# LaserScanner.net
KiCad netlist of a schematic drawn in EAGLE
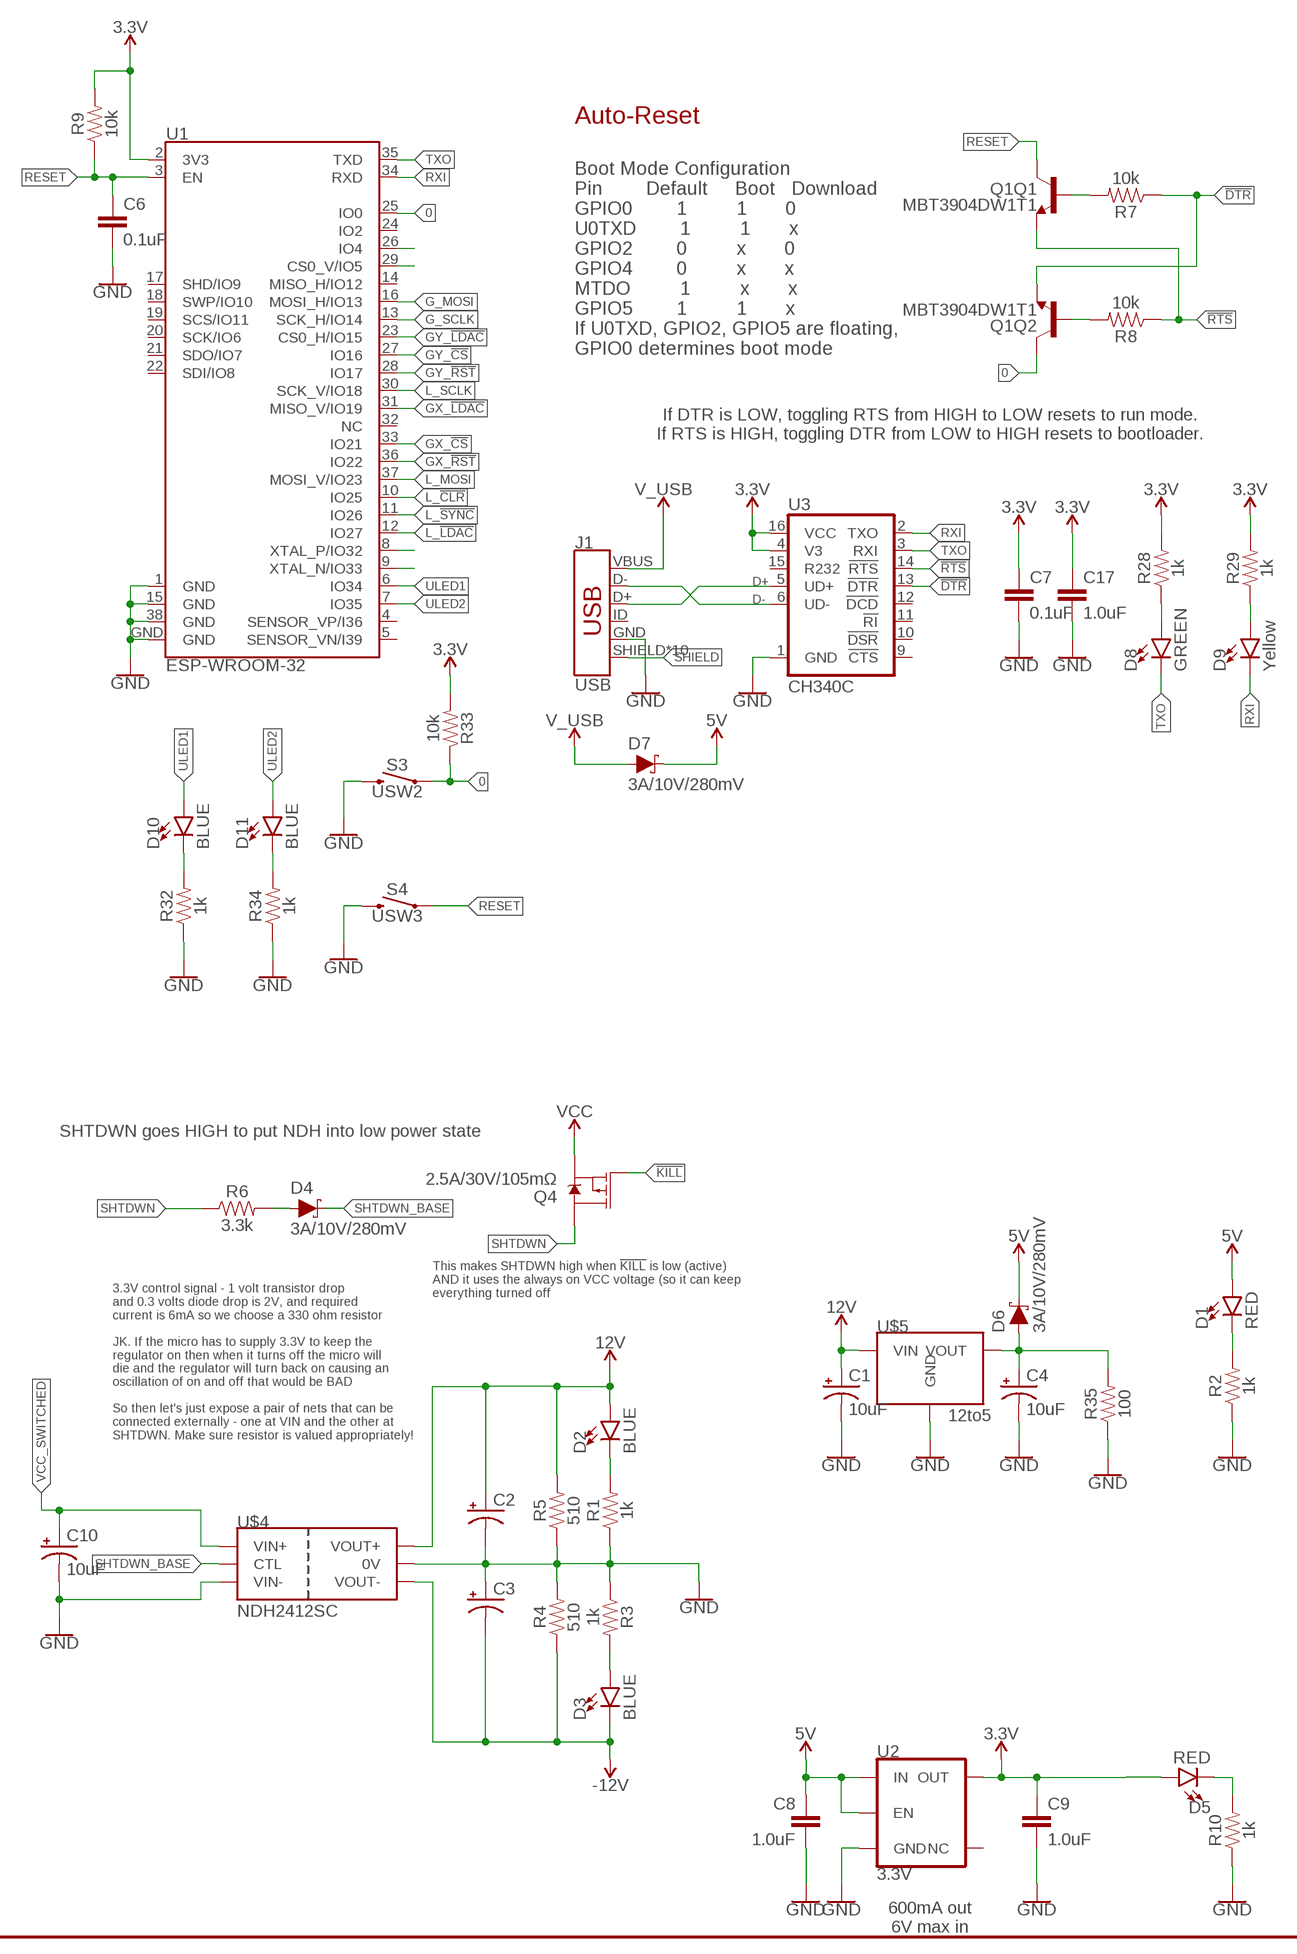
[diagram p0: schematic, sheet 1, part 1 of 2]
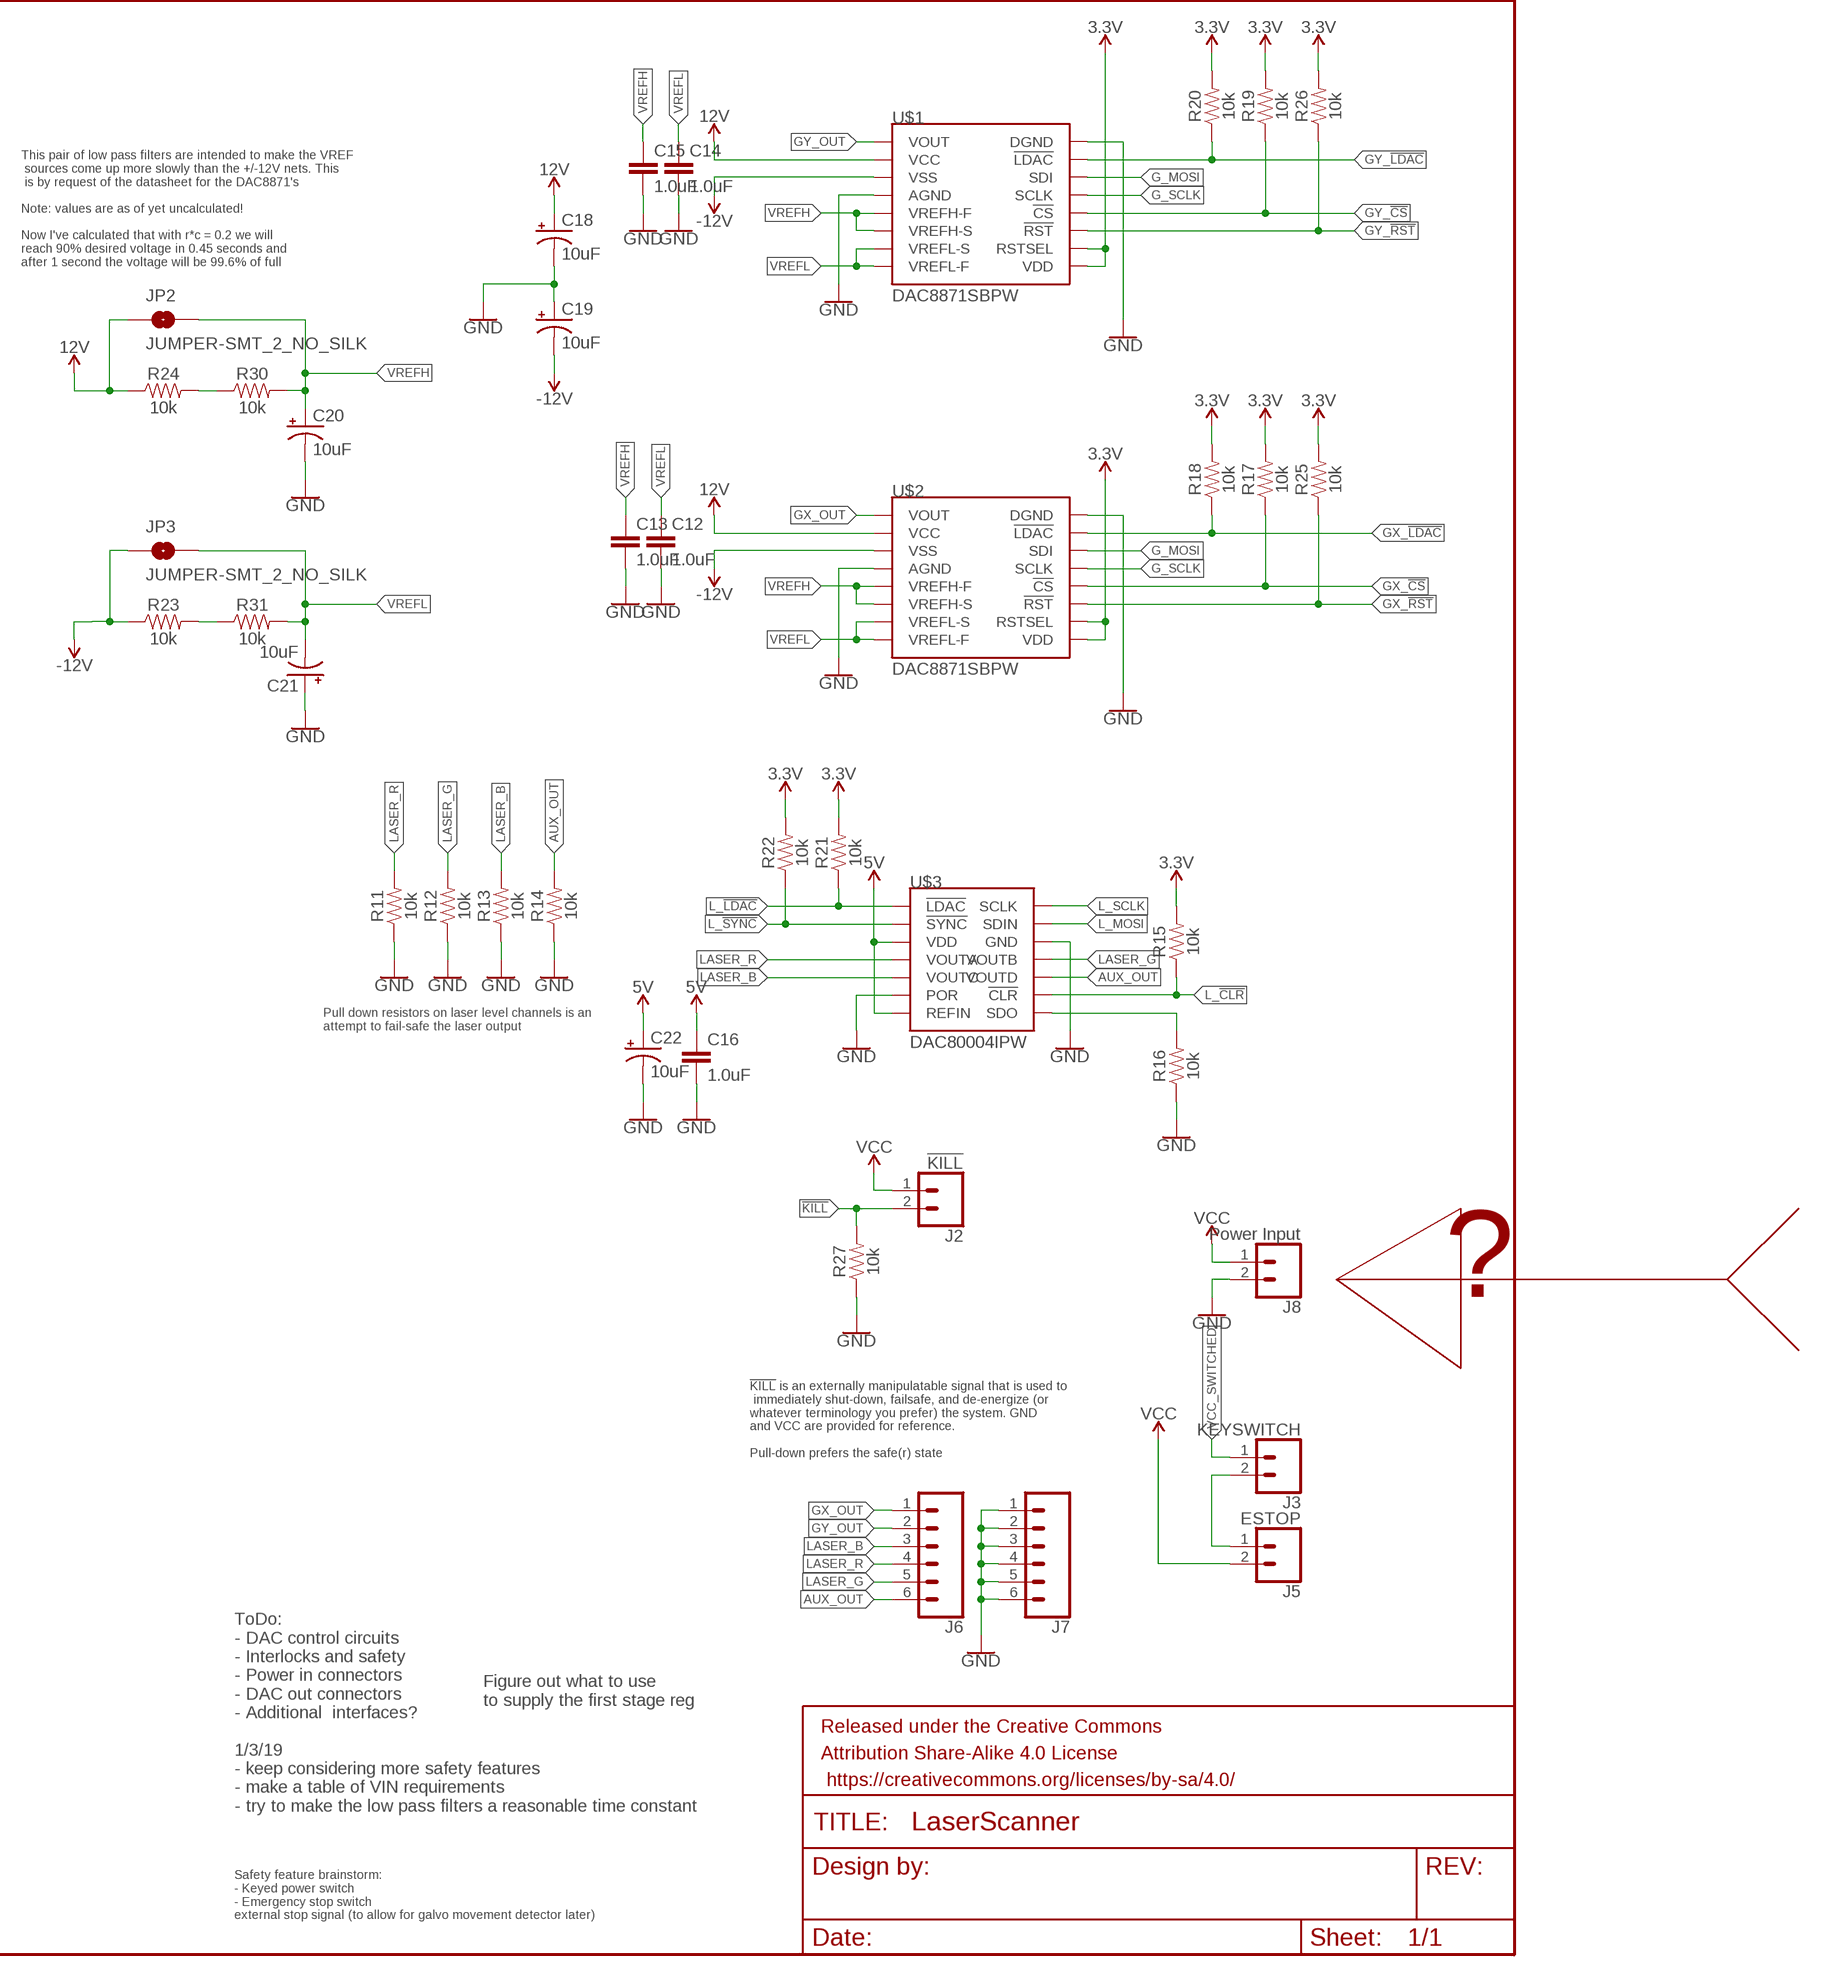
[diagram p1: schematic, sheet 1, part 2 of 2]

(export (version "E")
  (design (tool "Eeschema 10.0.6"))
  (components
    (comp (ref "C1")
      (value "10uF")
      (footprint "eagle-import:EIA3216")
      (libsource (lib "eagle-import") (part "10UF-POLAR-EIA3216-16V-10%(TANT)"))
    )
    (comp (ref "C2")
      (value "47UF-POLAR-PANASONIC_D-50V-20%")
      (footprint "eagle-import:PANASONIC_D")
      (libsource (lib "eagle-import") (part "47UF-POLAR-PANASONIC_D-50V-20%"))
    )
    (comp (ref "C3")
      (value "47UF-POLAR-PANASONIC_D-50V-20%")
      (footprint "eagle-import:PANASONIC_D")
      (libsource (lib "eagle-import") (part "47UF-POLAR-PANASONIC_D-50V-20%"))
    )
    (comp (ref "C4")
      (value "10uF")
      (footprint "eagle-import:EIA3216")
      (libsource (lib "eagle-import") (part "10UF-POLAR-EIA3216-16V-10%(TANT)"))
    )
    (comp (ref "C6")
      (value "0.1uF")
      (footprint "eagle-import:0603")
      (libsource (lib "eagle-import") (part "0.1UF-0603-25V-(+80/-20%)"))
    )
    (comp (ref "C7")
      (value "0.1uF")
      (footprint "eagle-import:0603")
      (libsource (lib "eagle-import") (part "0.1UF-0603-25V-5%"))
    )
    (comp (ref "C8")
      (value "1.0uF")
      (footprint "eagle-import:0603")
      (libsource (lib "eagle-import") (part "1.0UF-0603-16V-10%"))
    )
    (comp (ref "C9")
      (value "1.0uF")
      (footprint "eagle-import:0603")
      (libsource (lib "eagle-import") (part "1.0UF-0603-16V-10%"))
    )
    (comp (ref "C10")
      (value "10uF")
      (footprint "eagle-import:EIA3216")
      (libsource (lib "eagle-import") (part "10UF-POLAR-EIA3216-16V-10%(TANT)"))
    )
    (comp (ref "C12")
      (value "1.0uF")
      (footprint "eagle-import:0603")
      (libsource (lib "eagle-import") (part "1.0UF-0603-16V-10%-X7R"))
    )
    (comp (ref "C13")
      (value "1.0uF")
      (footprint "eagle-import:0603")
      (libsource (lib "eagle-import") (part "1.0UF-0603-16V-10%-X7R"))
    )
    (comp (ref "C14")
      (value "1.0uF")
      (footprint "eagle-import:0603")
      (libsource (lib "eagle-import") (part "1.0UF-0603-16V-10%-X7R"))
    )
    (comp (ref "C15")
      (value "1.0uF")
      (footprint "eagle-import:0603")
      (libsource (lib "eagle-import") (part "1.0UF-0603-16V-10%-X7R"))
    )
    (comp (ref "C16")
      (value "1.0uF")
      (footprint "eagle-import:0603")
      (libsource (lib "eagle-import") (part "1.0UF-0603-16V-10%-X7R"))
    )
    (comp (ref "C17")
      (value "1.0uF")
      (footprint "eagle-import:0603")
      (libsource (lib "eagle-import") (part "1.0UF-0603-16V-10%-X7R"))
    )
    (comp (ref "C18")
      (value "10uF")
      (footprint "eagle-import:EIA3216")
      (libsource (lib "eagle-import") (part "10UF-POLAR-EIA3216-16V-10%(TANT)"))
    )
    (comp (ref "C19")
      (value "10uF")
      (footprint "eagle-import:EIA3216")
      (libsource (lib "eagle-import") (part "10UF-POLAR-EIA3216-16V-10%(TANT)"))
    )
    (comp (ref "C20")
      (value "10uF")
      (footprint "eagle-import:EIA3216")
      (libsource (lib "eagle-import") (part "10UF-POLAR-EIA3216-16V-10%(TANT)"))
    )
    (comp (ref "C21")
      (value "10uF")
      (footprint "eagle-import:EIA3216")
      (libsource (lib "eagle-import") (part "10UF-POLAR-EIA3216-16V-10%(TANT)"))
    )
    (comp (ref "C22")
      (value "10uF")
      (footprint "eagle-import:EIA3216")
      (libsource (lib "eagle-import") (part "10UF-POLAR-EIA3216-16V-10%(TANT)"))
    )
    (comp (ref "D1")
      (value "RED")
      (footprint "eagle-import:LED-0603")
      (libsource (lib "eagle-import") (part "LED-RED0603"))
    )
    (comp (ref "D2")
      (value "BLUE")
      (footprint "eagle-import:LED-0603")
      (libsource (lib "eagle-import") (part "LED-BLUE0603"))
    )
    (comp (ref "D3")
      (value "BLUE")
      (footprint "eagle-import:LED-0603")
      (libsource (lib "eagle-import") (part "LED-BLUE0603"))
    )
    (comp (ref "D4")
      (value "3A/10V/280mV")
      (footprint "eagle-import:SOD-323")
      (libsource (lib "eagle-import") (part "DIODE-SCHOTTKY-BAT60A"))
    )
    (comp (ref "D5")
      (value "RED")
      (footprint "eagle-import:LED-0603")
      (libsource (lib "eagle-import") (part "LED-RED0603"))
    )
    (comp (ref "D6")
      (value "3A/10V/280mV")
      (footprint "eagle-import:SOD-323")
      (libsource (lib "eagle-import") (part "DIODE-SCHOTTKY-BAT60A"))
    )
    (comp (ref "D7")
      (value "3A/10V/280mV")
      (footprint "eagle-import:SOD-323")
      (libsource (lib "eagle-import") (part "DIODE-SCHOTTKY-BAT60A"))
    )
    (comp (ref "D8")
      (value "GREEN")
      (footprint "eagle-import:LED-0603")
      (libsource (lib "eagle-import") (part "LED-GREEN0603"))
    )
    (comp (ref "D9")
      (value "Yellow")
      (footprint "eagle-import:LED-0603")
      (libsource (lib "eagle-import") (part "LED-YELLOW0603"))
    )
    (comp (ref "D10")
      (value "BLUE")
      (footprint "eagle-import:LED-0603")
      (libsource (lib "eagle-import") (part "LED-BLUE0603"))
    )
    (comp (ref "D11")
      (value "BLUE")
      (footprint "eagle-import:LED-0603")
      (libsource (lib "eagle-import") (part "LED-BLUE0603"))
    )
    (comp (ref "FRAME1")
      (value "FRAME-LEDGER")
      (footprint "eagle-import:CREATIVE_COMMONS")
      (libsource (lib "eagle-import") (part "FRAME-LEDGER"))
    )
    (comp (ref "J1")
      (value "USB")
      (footprint "eagle-import:USB-MICROB-PTH-MILL")
      (libsource (lib "eagle-import") (part "USB_MICRO-B_HALF_PTH_MILL"))
    )
    (comp (ref "J2")
      (value "!KILL!")
      (footprint "eagle-import:1X02_NO_SILK")
      (libsource (lib "eagle-import") (part "CONN_021X02_NO_SILK"))
    )
    (comp (ref "J3")
      (value "KEYSWITCH")
      (footprint "eagle-import:1X02_NO_SILK")
      (libsource (lib "eagle-import") (part "CONN_021X02_NO_SILK"))
    )
    (comp (ref "J5")
      (value "ESTOP")
      (footprint "eagle-import:1X02_NO_SILK")
      (libsource (lib "eagle-import") (part "CONN_021X02_NO_SILK"))
    )
    (comp (ref "J6")
      (value "CONN_06NO_SILK_FEMALE_PTH")
      (footprint "eagle-import:1X06_NO_SILK")
      (libsource (lib "eagle-import") (part "CONN_06NO_SILK_FEMALE_PTH"))
    )
    (comp (ref "J7")
      (value "CONN_06NO_SILK_FEMALE_PTH")
      (footprint "eagle-import:1X06_NO_SILK")
      (libsource (lib "eagle-import") (part "CONN_06NO_SILK_FEMALE_PTH"))
    )
    (comp (ref "J8")
      (value "Power Input")
      (footprint "eagle-import:1X02_NO_SILK")
      (libsource (lib "eagle-import") (part "CONN_021X02_NO_SILK"))
    )
    (comp (ref "JP2")
      (value "JUMPER-SMT_2_NO_SILK")
      (footprint "eagle-import:SMT-JUMPER_2_NO_SILK")
      (libsource (lib "eagle-import") (part "JUMPER-SMT_2_NO_SILK"))
    )
    (comp (ref "JP3")
      (value "JUMPER-SMT_2_NO_SILK")
      (footprint "eagle-import:SMT-JUMPER_2_NO_SILK")
      (libsource (lib "eagle-import") (part "JUMPER-SMT_2_NO_SILK"))
    )
    (comp (ref "Q1")
      (value "MBT3904DW1T1")
      (footprint "eagle-import:SC70-6")
      (libsource (lib "eagle-import") (part "TRANS_NPN_DUAL-MBT3904DW1T1"))
    )
    (comp (ref "Q4")
      (value "2.5A/30V/105mΩ")
      (footprint "eagle-import:SOT23-3")
      (libsource (lib "eagle-import") (part "MOSFET_PCH-DMG2307L"))
    )
    (comp (ref "R1")
      (value "1k")
      (footprint "eagle-import:0603")
      (libsource (lib "eagle-import") (part "1KOHM-0603-1/10W-1%"))
    )
    (comp (ref "R2")
      (value "1k")
      (footprint "eagle-import:0603")
      (libsource (lib "eagle-import") (part "1KOHM-0603-1/10W-1%"))
    )
    (comp (ref "R3")
      (value "1k")
      (footprint "eagle-import:0603")
      (libsource (lib "eagle-import") (part "1KOHM-0603-1/10W-1%"))
    )
    (comp (ref "R4")
      (value "510")
      (footprint "eagle-import:2010")
      (libsource (lib "eagle-import") (part "510OHM-2010-1/2W-5%"))
    )
    (comp (ref "R5")
      (value "510")
      (footprint "eagle-import:2010")
      (libsource (lib "eagle-import") (part "510OHM-2010-1/2W-5%"))
    )
    (comp (ref "R6")
      (value "3.3k")
      (footprint "eagle-import:0603")
      (libsource (lib "eagle-import") (part "3.3KOHM-0603-1/10W-1%"))
    )
    (comp (ref "R7")
      (value "10k")
      (footprint "eagle-import:0603")
      (libsource (lib "eagle-import") (part "10KOHM-0603-1/10W-1%"))
    )
    (comp (ref "R8")
      (value "10k")
      (footprint "eagle-import:0603")
      (libsource (lib "eagle-import") (part "10KOHM-0603-1/10W-1%"))
    )
    (comp (ref "R9")
      (value "10k")
      (footprint "eagle-import:0603")
      (libsource (lib "eagle-import") (part "10KOHM-0603-1/10W-1%"))
    )
    (comp (ref "R10")
      (value "1k")
      (footprint "eagle-import:0603")
      (libsource (lib "eagle-import") (part "1KOHM-0603-1/10W-1%"))
    )
    (comp (ref "R11")
      (value "10k")
      (footprint "eagle-import:0603")
      (libsource (lib "eagle-import") (part "10KOHM-0603-1/10W-1%"))
    )
    (comp (ref "R12")
      (value "10k")
      (footprint "eagle-import:0603")
      (libsource (lib "eagle-import") (part "10KOHM-0603-1/10W-1%"))
    )
    (comp (ref "R13")
      (value "10k")
      (footprint "eagle-import:0603")
      (libsource (lib "eagle-import") (part "10KOHM-0603-1/10W-1%"))
    )
    (comp (ref "R14")
      (value "10k")
      (footprint "eagle-import:0603")
      (libsource (lib "eagle-import") (part "10KOHM-0603-1/10W-1%"))
    )
    (comp (ref "R15")
      (value "10k")
      (footprint "eagle-import:0603")
      (libsource (lib "eagle-import") (part "10KOHM-0603-1/10W-1%"))
    )
    (comp (ref "R16")
      (value "10k")
      (footprint "eagle-import:0603")
      (libsource (lib "eagle-import") (part "10KOHM-0603-1/10W-1%"))
    )
    (comp (ref "R17")
      (value "10k")
      (footprint "eagle-import:0603")
      (libsource (lib "eagle-import") (part "10KOHM-0603-1/10W-1%"))
    )
    (comp (ref "R18")
      (value "10k")
      (footprint "eagle-import:0603")
      (libsource (lib "eagle-import") (part "10KOHM-0603-1/10W-1%"))
    )
    (comp (ref "R19")
      (value "10k")
      (footprint "eagle-import:0603")
      (libsource (lib "eagle-import") (part "10KOHM-0603-1/10W-1%"))
    )
    (comp (ref "R20")
      (value "10k")
      (footprint "eagle-import:0603")
      (libsource (lib "eagle-import") (part "10KOHM-0603-1/10W-1%"))
    )
    (comp (ref "R21")
      (value "10k")
      (footprint "eagle-import:0603")
      (libsource (lib "eagle-import") (part "10KOHM-0603-1/10W-1%"))
    )
    (comp (ref "R22")
      (value "10k")
      (footprint "eagle-import:0603")
      (libsource (lib "eagle-import") (part "10KOHM-0603-1/10W-1%"))
    )
    (comp (ref "R23")
      (value "10k")
      (footprint "eagle-import:0603")
      (libsource (lib "eagle-import") (part "10KOHM-0603-1/10W-1%"))
    )
    (comp (ref "R24")
      (value "10k")
      (footprint "eagle-import:0603")
      (libsource (lib "eagle-import") (part "10KOHM-0603-1/10W-1%"))
    )
    (comp (ref "R25")
      (value "10k")
      (footprint "eagle-import:0603")
      (libsource (lib "eagle-import") (part "10KOHM-0603-1/10W-1%"))
    )
    (comp (ref "R26")
      (value "10k")
      (footprint "eagle-import:0603")
      (libsource (lib "eagle-import") (part "10KOHM-0603-1/10W-1%"))
    )
    (comp (ref "R27")
      (value "10k")
      (footprint "eagle-import:0603")
      (libsource (lib "eagle-import") (part "10KOHM-0603-1/10W-1%"))
    )
    (comp (ref "R28")
      (value "1k")
      (footprint "eagle-import:0603")
      (libsource (lib "eagle-import") (part "1KOHM-0603-1/10W-1%"))
    )
    (comp (ref "R29")
      (value "1k")
      (footprint "eagle-import:0603")
      (libsource (lib "eagle-import") (part "1KOHM-0603-1/10W-1%"))
    )
    (comp (ref "R30")
      (value "10k")
      (footprint "eagle-import:0603")
      (libsource (lib "eagle-import") (part "10KOHM-0603-1/10W-1%"))
    )
    (comp (ref "R31")
      (value "10k")
      (footprint "eagle-import:0603")
      (libsource (lib "eagle-import") (part "10KOHM-0603-1/10W-1%"))
    )
    (comp (ref "R32")
      (value "1k")
      (footprint "eagle-import:0603")
      (libsource (lib "eagle-import") (part "1KOHM-0603-1/10W-1%"))
    )
    (comp (ref "R33")
      (value "10k")
      (footprint "eagle-import:0603")
      (libsource (lib "eagle-import") (part "10KOHM-0603-1/10W-1%"))
    )
    (comp (ref "R34")
      (value "1k")
      (footprint "eagle-import:0603")
      (libsource (lib "eagle-import") (part "1KOHM-0603-1/10W-1%"))
    )
    (comp (ref "R35")
      (value "100")
      (footprint "eagle-import:0603")
      (libsource (lib "eagle-import") (part "100OHM-0603-1/4W-5%"))
    )
    (comp (ref "S3")
      (value "USW2")
      (footprint "eagle-import:TACTILE_SWITCH_SMD_5.2MM")
      (libsource (lib "eagle-import") (part "MOMENTARY-SWITCH-SPST-SMD-5.2-REDUNDANT"))
    )
    (comp (ref "S4")
      (value "USW3")
      (footprint "eagle-import:TACTILE_SWITCH_SMD_5.2MM")
      (libsource (lib "eagle-import") (part "MOMENTARY-SWITCH-SPST-SMD-5.2-REDUNDANT"))
    )
    (comp (ref "U$1")
      (value "DAC8871SBPW")
      (footprint "eagle-import:TSSOP16")
      (libsource (lib "eagle-import") (part "DAC8871SBPW"))
    )
    (comp (ref "U$2")
      (value "DAC8871SBPW")
      (footprint "eagle-import:TSSOP16")
      (libsource (lib "eagle-import") (part "DAC8871SBPW"))
    )
    (comp (ref "U$3")
      (value "DAC80004IPW")
      (footprint "eagle-import:TSSOP14")
      (libsource (lib "eagle-import") (part "DAC80004IPW"))
    )
    (comp (ref "U$4")
      (value "NDH2412SC")
      (footprint "eagle-import:NDH")
      (libsource (lib "eagle-import") (part "NDH2412SC"))
    )
    (comp (ref "U$5")
      (value "12to5")
      (footprint "eagle-import:RE-78E")
      (libsource (lib "eagle-import") (part "R-78E3.3-1.0"))
    )
    (comp (ref "U1")
      (value "ESP-WROOM-32")
      (footprint "eagle-import:ESP-WROOM-32")
      (libsource (lib "eagle-import") (part "ESP-WROOM-32"))
    )
    (comp (ref "U2")
      (value "3.3V")
      (footprint "eagle-import:SOT23-5")
      (libsource (lib "eagle-import") (part "V_REG_AP2112K-3.3V"))
    )
    (comp (ref "U3")
      (value "CH340C")
      (footprint "eagle-import:SO016")
      (libsource (lib "eagle-import") (part "CH340C"))
    )
  )
  (nets
    (net (code "1") (name "-12V") (class "Default")
      (node (ref "C19") (pin "-") (pinfunction "-_-") (pintype "passive"))
      (node (ref "C3") (pin "-") (pinfunction "-_-") (pintype "passive"))
      (node (ref "D3") (pin "C") (pinfunction "C_C") (pintype "passive"))
      (node (ref "JP3") (pin "1") (pinfunction "1_1") (pintype "passive"))
      (node (ref "R23") (pin "1") (pinfunction "1_1") (pintype "passive"))
      (node (ref "R4") (pin "1") (pinfunction "1_1") (pintype "passive"))
      (node (ref "U$1") (pin "3") (pinfunction "VSS_3") (pintype "bidirectional"))
      (node (ref "U$2") (pin "3") (pinfunction "VSS_3") (pintype "bidirectional"))
      (node (ref "U$4") (pin "9") (pinfunction "VOUT-_9") (pintype "bidirectional"))
    )
    (net (code "2") (name "/D+") (class "Default")
      (node (ref "J1") (pin "D+") (pinfunction "D+_D+") (pintype "bidirectional"))
      (node (ref "U3") (pin "5") (pinfunction "UD+_5") (pintype "bidirectional"))
    )
    (net (code "3") (name "/D-") (class "Default")
      (node (ref "J1") (pin "D-") (pinfunction "D-_D-") (pintype "bidirectional"))
      (node (ref "U3") (pin "6") (pinfunction "UD-_6") (pintype "bidirectional"))
    )
    (net (code "4") (name "/GX_~{CS}") (class "Default")
      (node (ref "R17") (pin "1") (pinfunction "1_1") (pintype "passive"))
      (node (ref "U$2") (pin "12") (pinfunction "~{CS}_12") (pintype "bidirectional"))
      (node (ref "U1") (pin "33") (pinfunction "IO21_33") (pintype "bidirectional"))
    )
    (net (code "5") (name "/GX_~{LDAC}") (class "Default")
      (node (ref "R18") (pin "1") (pinfunction "1_1") (pintype "passive"))
      (node (ref "U$2") (pin "15") (pinfunction "~{LDAC}_15") (pintype "bidirectional"))
      (node (ref "U1") (pin "31") (pinfunction "MISO_V/IO19_31") (pintype "bidirectional"))
    )
    (net (code "6") (name "/GX_~{RST}") (class "Default")
      (node (ref "R25") (pin "1") (pinfunction "1_1") (pintype "passive"))
      (node (ref "U$2") (pin "11") (pinfunction "~{RST}_11") (pintype "bidirectional"))
      (node (ref "U1") (pin "36") (pinfunction "IO22_36") (pintype "bidirectional"))
    )
    (net (code "7") (name "/GY_~{CS}") (class "Default")
      (node (ref "R19") (pin "1") (pinfunction "1_1") (pintype "passive"))
      (node (ref "U$1") (pin "12") (pinfunction "~{CS}_12") (pintype "bidirectional"))
      (node (ref "U1") (pin "27") (pinfunction "IO16_27") (pintype "bidirectional"))
    )
    (net (code "8") (name "/GY_~{LDAC}") (class "Default")
      (node (ref "R20") (pin "1") (pinfunction "1_1") (pintype "passive"))
      (node (ref "U$1") (pin "15") (pinfunction "~{LDAC}_15") (pintype "bidirectional"))
      (node (ref "U1") (pin "23") (pinfunction "CS0_H/IO15_23") (pintype "bidirectional"))
    )
    (net (code "9") (name "/GY_~{RST}") (class "Default")
      (node (ref "R26") (pin "1") (pinfunction "1_1") (pintype "passive"))
      (node (ref "U$1") (pin "11") (pinfunction "~{RST}_11") (pintype "bidirectional"))
      (node (ref "U1") (pin "28") (pinfunction "IO17_28") (pintype "bidirectional"))
    )
    (net (code "10") (name "/L_~{CLR}") (class "Default")
      (node (ref "R15") (pin "1") (pinfunction "1_1") (pintype "passive"))
      (node (ref "U$3") (pin "9") (pinfunction "~{CLR}_9") (pintype "bidirectional"))
      (node (ref "U1") (pin "10") (pinfunction "IO25_10") (pintype "bidirectional"))
    )
    (net (code "11") (name "/L_~{LDAC}") (class "Default")
      (node (ref "R21") (pin "1") (pinfunction "1_1") (pintype "passive"))
      (node (ref "U$3") (pin "1") (pinfunction "~{LDAC}_1") (pintype "bidirectional"))
      (node (ref "U1") (pin "12") (pinfunction "IO27_12") (pintype "bidirectional"))
    )
    (net (code "12") (name "/L_~{SYNC}") (class "Default")
      (node (ref "R22") (pin "1") (pinfunction "1_1") (pintype "passive"))
      (node (ref "U$3") (pin "2") (pinfunction "~{SYNC}_2") (pintype "bidirectional"))
      (node (ref "U1") (pin "11") (pinfunction "IO26_11") (pintype "bidirectional"))
    )
    (net (code "13") (name "/~{DTR}") (class "Default")
      (node (ref "Q1") (pin "1") (pinfunction "E_1") (pintype "passive"))
      (node (ref "R7") (pin "1") (pinfunction "1_1") (pintype "passive"))
      (node (ref "U3") (pin "13") (pinfunction "~{DTR}_13") (pintype "bidirectional"))
    )
    (net (code "14") (name "/~{KILL}") (class "Default")
      (node (ref "J2") (pin "2") (pinfunction "2_2") (pintype "passive"))
      (node (ref "Q4") (pin "1") (pinfunction "G_1") (pintype "bidirectional"))
      (node (ref "R27") (pin "2") (pinfunction "2_2") (pintype "passive"))
    )
    (net (code "15") (name "/~{RTS}") (class "Default")
      (node (ref "Q1") (pin "4") (pinfunction "E_4") (pintype "passive"))
      (node (ref "R8") (pin "1") (pinfunction "1_1") (pintype "passive"))
      (node (ref "U3") (pin "14") (pinfunction "~{RTS}_14") (pintype "bidirectional"))
    )
    (net (code "16") (name "0") (class "Default")
      (node (ref "Q1") (pin "6") (pinfunction "C_6") (pintype "passive"))
      (node (ref "R33") (pin "1") (pinfunction "1_1") (pintype "passive"))
      (node (ref "S3") (pin "1") (pinfunction "1_1") (pintype "passive"))
      (node (ref "S3") (pin "2") (pinfunction "1_2") (pintype "passive"))
      (node (ref "U1") (pin "25") (pinfunction "IO0_25") (pintype "bidirectional"))
    )
    (net (code "17") (name "3.3V") (class "Default")
      (node (ref "C17") (pin "1") (pinfunction "1_1") (pintype "passive"))
      (node (ref "C7") (pin "1") (pinfunction "1_1") (pintype "passive"))
      (node (ref "C9") (pin "1") (pinfunction "1_1") (pintype "passive"))
      (node (ref "D5") (pin "A") (pinfunction "A_A") (pintype "passive"))
      (node (ref "R15") (pin "2") (pinfunction "2_2") (pintype "passive"))
      (node (ref "R17") (pin "2") (pinfunction "2_2") (pintype "passive"))
      (node (ref "R18") (pin "2") (pinfunction "2_2") (pintype "passive"))
      (node (ref "R19") (pin "2") (pinfunction "2_2") (pintype "passive"))
      (node (ref "R20") (pin "2") (pinfunction "2_2") (pintype "passive"))
      (node (ref "R21") (pin "2") (pinfunction "2_2") (pintype "passive"))
      (node (ref "R22") (pin "2") (pinfunction "2_2") (pintype "passive"))
      (node (ref "R25") (pin "2") (pinfunction "2_2") (pintype "passive"))
      (node (ref "R26") (pin "2") (pinfunction "2_2") (pintype "passive"))
      (node (ref "R28") (pin "2") (pinfunction "2_2") (pintype "passive"))
      (node (ref "R29") (pin "2") (pinfunction "2_2") (pintype "passive"))
      (node (ref "R33") (pin "2") (pinfunction "2_2") (pintype "passive"))
      (node (ref "R9") (pin "2") (pinfunction "2_2") (pintype "passive"))
      (node (ref "U$1") (pin "10") (pinfunction "RSTSEL_10") (pintype "bidirectional"))
      (node (ref "U$1") (pin "9") (pinfunction "VDD_9") (pintype "bidirectional"))
      (node (ref "U$2") (pin "10") (pinfunction "RSTSEL_10") (pintype "bidirectional"))
      (node (ref "U$2") (pin "9") (pinfunction "VDD_9") (pintype "bidirectional"))
      (node (ref "U1") (pin "2") (pinfunction "3V3_2") (pintype "bidirectional"))
      (node (ref "U2") (pin "5") (pinfunction "OUT_5") (pintype "passive"))
      (node (ref "U3") (pin "16") (pinfunction "VCC_16") (pintype "bidirectional"))
      (node (ref "U3") (pin "4") (pinfunction "V3_4") (pintype "bidirectional"))
    )
    (net (code "18") (name "5V") (class "Default")
      (node (ref "C16") (pin "1") (pinfunction "1_1") (pintype "passive"))
      (node (ref "C22") (pin "+") (pinfunction "+_+") (pintype "passive"))
      (node (ref "C8") (pin "1") (pinfunction "1_1") (pintype "passive"))
      (node (ref "D1") (pin "A") (pinfunction "A_A") (pintype "passive"))
      (node (ref "D6") (pin "C") (pinfunction "C_C") (pintype "passive"))
      (node (ref "D7") (pin "C") (pinfunction "C_C") (pintype "passive"))
      (node (ref "U$3") (pin "3") (pinfunction "VDD_3") (pintype "bidirectional"))
      (node (ref "U$3") (pin "7") (pinfunction "REFIN_7") (pintype "bidirectional"))
      (node (ref "U2") (pin "1") (pinfunction "IN_1") (pintype "input"))
      (node (ref "U2") (pin "3") (pinfunction "EN_3") (pintype "input"))
    )
    (net (code "19") (name "12V") (class "Default")
      (node (ref "C1") (pin "+") (pinfunction "+_+") (pintype "passive"))
      (node (ref "C18") (pin "+") (pinfunction "+_+") (pintype "passive"))
      (node (ref "C2") (pin "+") (pinfunction "+_+") (pintype "passive"))
      (node (ref "D2") (pin "A") (pinfunction "A_A") (pintype "passive"))
      (node (ref "JP2") (pin "1") (pinfunction "1_1") (pintype "passive"))
      (node (ref "R24") (pin "1") (pinfunction "1_1") (pintype "passive"))
      (node (ref "R5") (pin "2") (pinfunction "2_2") (pintype "passive"))
      (node (ref "U$1") (pin "2") (pinfunction "VCC_2") (pintype "bidirectional"))
      (node (ref "U$2") (pin "2") (pinfunction "VCC_2") (pintype "bidirectional"))
      (node (ref "U$4") (pin "6") (pinfunction "VOUT+_6") (pintype "bidirectional"))
      (node (ref "U$5") (pin "1") (pinfunction "VIN_1") (pintype "bidirectional"))
    )
    (net (code "20") (name "AUX_OUT") (class "Default")
      (node (ref "J6") (pin "6") (pinfunction "6_6") (pintype "passive"))
      (node (ref "R14") (pin "2") (pinfunction "2_2") (pintype "passive"))
      (node (ref "U$3") (pin "10") (pinfunction "VOUTD_10") (pintype "bidirectional"))
    )
    (net (code "21") (name "GND") (class "Default")
      (node (ref "C1") (pin "-") (pinfunction "-_-") (pintype "passive"))
      (node (ref "C10") (pin "-") (pinfunction "-_-") (pintype "passive"))
      (node (ref "C12") (pin "2") (pinfunction "2_2") (pintype "passive"))
      (node (ref "C13") (pin "2") (pinfunction "2_2") (pintype "passive"))
      (node (ref "C14") (pin "2") (pinfunction "2_2") (pintype "passive"))
      (node (ref "C15") (pin "2") (pinfunction "2_2") (pintype "passive"))
      (node (ref "C16") (pin "2") (pinfunction "2_2") (pintype "passive"))
      (node (ref "C17") (pin "2") (pinfunction "2_2") (pintype "passive"))
      (node (ref "C18") (pin "-") (pinfunction "-_-") (pintype "passive"))
      (node (ref "C19") (pin "+") (pinfunction "+_+") (pintype "passive"))
      (node (ref "C2") (pin "-") (pinfunction "-_-") (pintype "passive"))
      (node (ref "C20") (pin "-") (pinfunction "-_-") (pintype "passive"))
      (node (ref "C21") (pin "+") (pinfunction "+_+") (pintype "passive"))
      (node (ref "C22") (pin "-") (pinfunction "-_-") (pintype "passive"))
      (node (ref "C3") (pin "+") (pinfunction "+_+") (pintype "passive"))
      (node (ref "C4") (pin "-") (pinfunction "-_-") (pintype "passive"))
      (node (ref "C6") (pin "2") (pinfunction "2_2") (pintype "passive"))
      (node (ref "C7") (pin "2") (pinfunction "2_2") (pintype "passive"))
      (node (ref "C8") (pin "2") (pinfunction "2_2") (pintype "passive"))
      (node (ref "C9") (pin "2") (pinfunction "2_2") (pintype "passive"))
      (node (ref "J1") (pin "GND") (pinfunction "GND_GND") (pintype "power_in"))
      (node (ref "J7") (pin "1") (pinfunction "1_1") (pintype "passive"))
      (node (ref "J7") (pin "2") (pinfunction "2_2") (pintype "passive"))
      (node (ref "J7") (pin "3") (pinfunction "3_3") (pintype "passive"))
      (node (ref "J7") (pin "4") (pinfunction "4_4") (pintype "passive"))
      (node (ref "J7") (pin "5") (pinfunction "5_5") (pintype "passive"))
      (node (ref "J7") (pin "6") (pinfunction "6_6") (pintype "passive"))
      (node (ref "J8") (pin "2") (pinfunction "2_2") (pintype "passive"))
      (node (ref "R1") (pin "1") (pinfunction "1_1") (pintype "passive"))
      (node (ref "R10") (pin "1") (pinfunction "1_1") (pintype "passive"))
      (node (ref "R11") (pin "1") (pinfunction "1_1") (pintype "passive"))
      (node (ref "R12") (pin "1") (pinfunction "1_1") (pintype "passive"))
      (node (ref "R13") (pin "1") (pinfunction "1_1") (pintype "passive"))
      (node (ref "R14") (pin "1") (pinfunction "1_1") (pintype "passive"))
      (node (ref "R16") (pin "1") (pinfunction "1_1") (pintype "passive"))
      (node (ref "R2") (pin "1") (pinfunction "1_1") (pintype "passive"))
      (node (ref "R27") (pin "1") (pinfunction "1_1") (pintype "passive"))
      (node (ref "R3") (pin "1") (pinfunction "1_1") (pintype "passive"))
      (node (ref "R32") (pin "1") (pinfunction "1_1") (pintype "passive"))
      (node (ref "R34") (pin "1") (pinfunction "1_1") (pintype "passive"))
      (node (ref "R35") (pin "1") (pinfunction "1_1") (pintype "passive"))
      (node (ref "R4") (pin "2") (pinfunction "2_2") (pintype "passive"))
      (node (ref "R5") (pin "1") (pinfunction "1_1") (pintype "passive"))
      (node (ref "S3") (pin "3") (pinfunction "2_3") (pintype "passive"))
      (node (ref "S3") (pin "4") (pinfunction "2_4") (pintype "passive"))
      (node (ref "S4") (pin "3") (pinfunction "2_3") (pintype "passive"))
      (node (ref "S4") (pin "4") (pinfunction "2_4") (pintype "passive"))
      (node (ref "U$1") (pin "16") (pinfunction "DGND_16") (pintype "bidirectional"))
      (node (ref "U$1") (pin "4") (pinfunction "AGND_4") (pintype "bidirectional"))
      (node (ref "U$2") (pin "16") (pinfunction "DGND_16") (pintype "bidirectional"))
      (node (ref "U$2") (pin "4") (pinfunction "AGND_4") (pintype "bidirectional"))
      (node (ref "U$3") (pin "12") (pinfunction "GND_12") (pintype "bidirectional"))
      (node (ref "U$3") (pin "6") (pinfunction "POR_6") (pintype "bidirectional"))
      (node (ref "U$4") (pin "1") (pinfunction "VIN-_1") (pintype "bidirectional"))
      (node (ref "U$4") (pin "7") (pinfunction "0V_7") (pintype "bidirectional"))
      (node (ref "U$5") (pin "2") (pinfunction "GND_2") (pintype "bidirectional"))
      (node (ref "U1") (pin "1") (pinfunction "GND_1") (pintype "bidirectional"))
      (node (ref "U1") (pin "15") (pinfunction "GND_15") (pintype "bidirectional"))
      (node (ref "U1") (pin "38") (pinfunction "GND_38") (pintype "bidirectional"))
      (node (ref "U1") (pin "GND") (pinfunction "GND_GND") (pintype "bidirectional"))
      (node (ref "U2") (pin "2") (pinfunction "GND_2") (pintype "input"))
      (node (ref "U3") (pin "1") (pinfunction "GND_1") (pintype "bidirectional"))
    )
    (net (code "22") (name "GX_OUT") (class "Default")
      (node (ref "J6") (pin "1") (pinfunction "1_1") (pintype "passive"))
      (node (ref "U$2") (pin "1") (pinfunction "VOUT_1") (pintype "bidirectional"))
    )
    (net (code "23") (name "GY_OUT") (class "Default")
      (node (ref "J6") (pin "2") (pinfunction "2_2") (pintype "passive"))
      (node (ref "U$1") (pin "1") (pinfunction "VOUT_1") (pintype "bidirectional"))
    )
    (net (code "24") (name "G_MOSI") (class "Default")
      (node (ref "U$1") (pin "14") (pinfunction "SDI_14") (pintype "bidirectional"))
      (node (ref "U$2") (pin "14") (pinfunction "SDI_14") (pintype "bidirectional"))
      (node (ref "U1") (pin "16") (pinfunction "MOSI_H/IO13_16") (pintype "bidirectional"))
    )
    (net (code "25") (name "G_SCLK") (class "Default")
      (node (ref "U$1") (pin "13") (pinfunction "SCLK_13") (pintype "bidirectional"))
      (node (ref "U$2") (pin "13") (pinfunction "SCLK_13") (pintype "bidirectional"))
      (node (ref "U1") (pin "13") (pinfunction "SCK_H/IO14_13") (pintype "bidirectional"))
    )
    (net (code "26") (name "LASER_B") (class "Default")
      (node (ref "J6") (pin "3") (pinfunction "3_3") (pintype "passive"))
      (node (ref "R13") (pin "2") (pinfunction "2_2") (pintype "passive"))
      (node (ref "U$3") (pin "5") (pinfunction "VOUTC_5") (pintype "bidirectional"))
    )
    (net (code "27") (name "LASER_G") (class "Default")
      (node (ref "J6") (pin "5") (pinfunction "5_5") (pintype "passive"))
      (node (ref "R12") (pin "2") (pinfunction "2_2") (pintype "passive"))
      (node (ref "U$3") (pin "11") (pinfunction "VOUTB_11") (pintype "bidirectional"))
    )
    (net (code "28") (name "LASER_R") (class "Default")
      (node (ref "J6") (pin "4") (pinfunction "4_4") (pintype "passive"))
      (node (ref "R11") (pin "2") (pinfunction "2_2") (pintype "passive"))
      (node (ref "U$3") (pin "4") (pinfunction "VOUTA_4") (pintype "bidirectional"))
    )
    (net (code "29") (name "L_MOSI") (class "Default")
      (node (ref "U$3") (pin "13") (pinfunction "SDIN_13") (pintype "bidirectional"))
      (node (ref "U1") (pin "37") (pinfunction "MOSI_V/IO23_37") (pintype "bidirectional"))
    )
    (net (code "30") (name "L_SCLK") (class "Default")
      (node (ref "U$3") (pin "14") (pinfunction "SCLK_14") (pintype "bidirectional"))
      (node (ref "U1") (pin "30") (pinfunction "SCK_V/IO18_30") (pintype "bidirectional"))
    )
    (net (code "31") (name "Net-(D1-PadC)") (class "Default")
      (node (ref "D1") (pin "C") (pinfunction "C_C") (pintype "passive"))
      (node (ref "R2") (pin "2") (pinfunction "2_2") (pintype "passive"))
    )
    (net (code "32") (name "Net-(D2-PadC)") (class "Default")
      (node (ref "D2") (pin "C") (pinfunction "C_C") (pintype "passive"))
      (node (ref "R1") (pin "2") (pinfunction "2_2") (pintype "passive"))
    )
    (net (code "33") (name "Net-(D3-PadA)") (class "Default")
      (node (ref "D3") (pin "A") (pinfunction "A_A") (pintype "passive"))
      (node (ref "R3") (pin "2") (pinfunction "2_2") (pintype "passive"))
    )
    (net (code "34") (name "Net-(D4-PadA)") (class "Default")
      (node (ref "D4") (pin "A") (pinfunction "A_A") (pintype "passive"))
      (node (ref "R6") (pin "2") (pinfunction "2_2") (pintype "passive"))
    )
    (net (code "35") (name "Net-(D5-PadC)") (class "Default")
      (node (ref "D5") (pin "C") (pinfunction "C_C") (pintype "passive"))
      (node (ref "R10") (pin "2") (pinfunction "2_2") (pintype "passive"))
    )
    (net (code "36") (name "Net-(D8-PadA)") (class "Default")
      (node (ref "D8") (pin "A") (pinfunction "A_A") (pintype "passive"))
      (node (ref "R28") (pin "1") (pinfunction "1_1") (pintype "passive"))
    )
    (net (code "37") (name "Net-(D9-PadA)") (class "Default")
      (node (ref "D9") (pin "A") (pinfunction "A_A") (pintype "passive"))
      (node (ref "R29") (pin "1") (pinfunction "1_1") (pintype "passive"))
    )
    (net (code "38") (name "Net-(D10-PadC)") (class "Default")
      (node (ref "D10") (pin "C") (pinfunction "C_C") (pintype "passive"))
      (node (ref "R32") (pin "2") (pinfunction "2_2") (pintype "passive"))
    )
    (net (code "39") (name "Net-(D11-PadC)") (class "Default")
      (node (ref "D11") (pin "C") (pinfunction "C_C") (pintype "passive"))
      (node (ref "R34") (pin "2") (pinfunction "2_2") (pintype "passive"))
    )
    (net (code "40") (name "Net-(J3-Pad2)") (class "Default")
      (node (ref "J3") (pin "2") (pinfunction "2_2") (pintype "passive"))
      (node (ref "J5") (pin "1") (pinfunction "1_1") (pintype "passive"))
    )
    (net (code "41") (name "Net-(Q1A-B)") (class "Default")
      (node (ref "Q1") (pin "5") (pinfunction "B_5") (pintype "passive"))
      (node (ref "R7") (pin "2") (pinfunction "2_2") (pintype "passive"))
    )
    (net (code "42") (name "Net-(Q1B-B)") (class "Default")
      (node (ref "Q1") (pin "2") (pinfunction "B_2") (pintype "passive"))
      (node (ref "R8") (pin "2") (pinfunction "2_2") (pintype "passive"))
    )
    (net (code "43") (name "Net-(R23-Pad2)") (class "Default")
      (node (ref "R23") (pin "2") (pinfunction "2_2") (pintype "passive"))
      (node (ref "R31") (pin "1") (pinfunction "1_1") (pintype "passive"))
    )
    (net (code "44") (name "Net-(R24-Pad2)") (class "Default")
      (node (ref "R24") (pin "2") (pinfunction "2_2") (pintype "passive"))
      (node (ref "R30") (pin "1") (pinfunction "1_1") (pintype "passive"))
    )
    (net (code "45") (name "Net-(U$3-SDO)") (class "Default")
      (node (ref "R16") (pin "2") (pinfunction "2_2") (pintype "passive"))
      (node (ref "U$3") (pin "8") (pinfunction "SDO_8") (pintype "bidirectional"))
    )
    (net (code "46") (name "Net-(U$5-VOUT)") (class "Default")
      (node (ref "C4") (pin "+") (pinfunction "+_+") (pintype "passive"))
      (node (ref "D6") (pin "A") (pinfunction "A_A") (pintype "passive"))
      (node (ref "R35") (pin "2") (pinfunction "2_2") (pintype "passive"))
      (node (ref "U$5") (pin "3") (pinfunction "VOUT_3") (pintype "bidirectional"))
    )
    (net (code "47") (name "RESET") (class "Default")
      (node (ref "C6") (pin "1") (pinfunction "1_1") (pintype "passive"))
      (node (ref "Q1") (pin "3") (pinfunction "C_3") (pintype "passive"))
      (node (ref "R9") (pin "1") (pinfunction "1_1") (pintype "passive"))
      (node (ref "S4") (pin "1") (pinfunction "1_1") (pintype "passive"))
      (node (ref "S4") (pin "2") (pinfunction "1_2") (pintype "passive"))
      (node (ref "U1") (pin "3") (pinfunction "EN_3") (pintype "bidirectional"))
    )
    (net (code "48") (name "RXI") (class "Default")
      (node (ref "D9") (pin "C") (pinfunction "C_C") (pintype "passive"))
      (node (ref "U1") (pin "34") (pinfunction "RXD_34") (pintype "bidirectional"))
      (node (ref "U3") (pin "2") (pinfunction "TXO_2") (pintype "bidirectional"))
    )
    (net (code "49") (name "SHIELD") (class "Default")
      (node (ref "J1") (pin "SHIELD") (pinfunction "SHIELD_SHIELD") (pintype "bidirectional"))
      (node (ref "J1") (pin "SHIELD10") (pinfunction "SHIELD_SHIELD10") (pintype "bidirectional"))
      (node (ref "J1") (pin "SHIELD2") (pinfunction "SHIELD_SHIELD2") (pintype "bidirectional"))
      (node (ref "J1") (pin "SHIELD3") (pinfunction "SHIELD_SHIELD3") (pintype "bidirectional"))
      (node (ref "J1") (pin "SHIELD4") (pinfunction "SHIELD_SHIELD4") (pintype "bidirectional"))
      (node (ref "J1") (pin "SHIELD5") (pinfunction "SHIELD_SHIELD5") (pintype "bidirectional"))
      (node (ref "J1") (pin "SHIELD6") (pinfunction "SHIELD_SHIELD6") (pintype "bidirectional"))
      (node (ref "J1") (pin "SHIELD7") (pinfunction "SHIELD_SHIELD7") (pintype "bidirectional"))
      (node (ref "J1") (pin "SHIELD8") (pinfunction "SHIELD_SHIELD8") (pintype "bidirectional"))
      (node (ref "J1") (pin "SHIELD9") (pinfunction "SHIELD_SHIELD9") (pintype "bidirectional"))
    )
    (net (code "50") (name "SHTDWN") (class "Default")
      (node (ref "Q4") (pin "3") (pinfunction "D_3") (pintype "bidirectional"))
      (node (ref "R6") (pin "1") (pinfunction "1_1") (pintype "passive"))
    )
    (net (code "51") (name "SHTDWN_BASE") (class "Default")
      (node (ref "D4") (pin "C") (pinfunction "C_C") (pintype "passive"))
      (node (ref "U$4") (pin "3") (pinfunction "CTL_3") (pintype "bidirectional"))
    )
    (net (code "52") (name "TXO") (class "Default")
      (node (ref "D8") (pin "C") (pinfunction "C_C") (pintype "passive"))
      (node (ref "U1") (pin "35") (pinfunction "TXD_35") (pintype "bidirectional"))
      (node (ref "U3") (pin "3") (pinfunction "RXI_3") (pintype "bidirectional"))
    )
    (net (code "53") (name "ULED1") (class "Default")
      (node (ref "D10") (pin "A") (pinfunction "A_A") (pintype "passive"))
      (node (ref "U1") (pin "6") (pinfunction "IO34_6") (pintype "bidirectional"))
    )
    (net (code "54") (name "ULED2") (class "Default")
      (node (ref "D11") (pin "A") (pinfunction "A_A") (pintype "passive"))
      (node (ref "U1") (pin "7") (pinfunction "IO35_7") (pintype "bidirectional"))
    )
    (net (code "55") (name "VCC") (class "Default")
      (node (ref "J2") (pin "1") (pinfunction "1_1") (pintype "passive"))
      (node (ref "J5") (pin "2") (pinfunction "2_2") (pintype "passive"))
      (node (ref "J8") (pin "1") (pinfunction "1_1") (pintype "passive"))
      (node (ref "Q4") (pin "2") (pinfunction "S_2") (pintype "bidirectional"))
    )
    (net (code "56") (name "VCC_SWITCHED") (class "Default")
      (node (ref "C10") (pin "+") (pinfunction "+_+") (pintype "passive"))
      (node (ref "J3") (pin "1") (pinfunction "1_1") (pintype "passive"))
      (node (ref "U$4") (pin "2") (pinfunction "VIN+_2") (pintype "bidirectional"))
    )
    (net (code "57") (name "VREFH") (class "Default")
      (node (ref "C13") (pin "1") (pinfunction "1_1") (pintype "passive"))
      (node (ref "C15") (pin "1") (pinfunction "1_1") (pintype "passive"))
      (node (ref "C20") (pin "+") (pinfunction "+_+") (pintype "passive"))
      (node (ref "JP2") (pin "2") (pinfunction "2_2") (pintype "passive"))
      (node (ref "R30") (pin "2") (pinfunction "2_2") (pintype "passive"))
      (node (ref "U$1") (pin "5") (pinfunction "VREFH-F_5") (pintype "bidirectional"))
      (node (ref "U$1") (pin "6") (pinfunction "VREFH-S_6") (pintype "bidirectional"))
      (node (ref "U$2") (pin "5") (pinfunction "VREFH-F_5") (pintype "bidirectional"))
      (node (ref "U$2") (pin "6") (pinfunction "VREFH-S_6") (pintype "bidirectional"))
    )
    (net (code "58") (name "VREFL") (class "Default")
      (node (ref "C12") (pin "1") (pinfunction "1_1") (pintype "passive"))
      (node (ref "C14") (pin "1") (pinfunction "1_1") (pintype "passive"))
      (node (ref "C21") (pin "-") (pinfunction "-_-") (pintype "passive"))
      (node (ref "JP3") (pin "2") (pinfunction "2_2") (pintype "passive"))
      (node (ref "R31") (pin "2") (pinfunction "2_2") (pintype "passive"))
      (node (ref "U$1") (pin "7") (pinfunction "VREFL-S_7") (pintype "bidirectional"))
      (node (ref "U$1") (pin "8") (pinfunction "VREFL-F_8") (pintype "bidirectional"))
      (node (ref "U$2") (pin "7") (pinfunction "VREFL-S_7") (pintype "bidirectional"))
      (node (ref "U$2") (pin "8") (pinfunction "VREFL-F_8") (pintype "bidirectional"))
    )
    (net (code "59") (name "V_USB") (class "Default")
      (node (ref "D7") (pin "A") (pinfunction "A_A") (pintype "passive"))
      (node (ref "J1") (pin "VBUS") (pinfunction "VBUS_VBUS") (pintype "power_in"))
    )
    (net (code "60") (name "unconnected-(J1-PadID)") (class "Default")
      (node (ref "J1") (pin "ID") (pinfunction "ID_ID") (pintype "bidirectional"))
    )
    (net (code "61") (name "unconnected-(U1-CS0_V{slash}IO5-Pad29)") (class "Default")
      (node (ref "U1") (pin "29") (pinfunction "CS0_V/IO5_29") (pintype "bidirectional"))
    )
    (net (code "62") (name "unconnected-(U1-IO2-Pad24)") (class "Default")
      (node (ref "U1") (pin "24") (pinfunction "IO2_24") (pintype "bidirectional"))
    )
    (net (code "63") (name "unconnected-(U1-IO4-Pad26)") (class "Default")
      (node (ref "U1") (pin "26") (pinfunction "IO4_26") (pintype "bidirectional"))
    )
    (net (code "64") (name "unconnected-(U1-MISO_H{slash}IO12-Pad14)") (class "Default")
      (node (ref "U1") (pin "14") (pinfunction "MISO_H/IO12_14") (pintype "bidirectional"))
    )
    (net (code "65") (name "unconnected-(U1-NC-Pad32)") (class "Default")
      (node (ref "U1") (pin "32") (pinfunction "NC_32") (pintype "bidirectional"))
    )
    (net (code "66") (name "unconnected-(U1-SCK{slash}IO6-Pad20)") (class "Default")
      (node (ref "U1") (pin "20") (pinfunction "SCK/IO6_20") (pintype "bidirectional"))
    )
    (net (code "67") (name "unconnected-(U1-SCS{slash}IO11-Pad19)") (class "Default")
      (node (ref "U1") (pin "19") (pinfunction "SCS/IO11_19") (pintype "bidirectional"))
    )
    (net (code "68") (name "unconnected-(U1-SDI{slash}IO8-Pad22)") (class "Default")
      (node (ref "U1") (pin "22") (pinfunction "SDI/IO8_22") (pintype "bidirectional"))
    )
    (net (code "69") (name "unconnected-(U1-SDO{slash}IO7-Pad21)") (class "Default")
      (node (ref "U1") (pin "21") (pinfunction "SDO/IO7_21") (pintype "bidirectional"))
    )
    (net (code "70") (name "unconnected-(U1-SENSOR_VN{slash}I39-Pad5)") (class "Default")
      (node (ref "U1") (pin "5") (pinfunction "SENSOR_VN/I39_5") (pintype "bidirectional"))
    )
    (net (code "71") (name "unconnected-(U1-SENSOR_VP{slash}I36-Pad4)") (class "Default")
      (node (ref "U1") (pin "4") (pinfunction "SENSOR_VP/I36_4") (pintype "bidirectional"))
    )
    (net (code "72") (name "unconnected-(U1-SHD{slash}IO9-Pad17)") (class "Default")
      (node (ref "U1") (pin "17") (pinfunction "SHD/IO9_17") (pintype "bidirectional"))
    )
    (net (code "73") (name "unconnected-(U1-SWP{slash}IO10-Pad18)") (class "Default")
      (node (ref "U1") (pin "18") (pinfunction "SWP/IO10_18") (pintype "bidirectional"))
    )
    (net (code "74") (name "unconnected-(U1-XTAL_N{slash}IO33-Pad9)") (class "Default")
      (node (ref "U1") (pin "9") (pinfunction "XTAL_N/IO33_9") (pintype "bidirectional"))
    )
    (net (code "75") (name "unconnected-(U1-XTAL_P{slash}IO32-Pad8)") (class "Default")
      (node (ref "U1") (pin "8") (pinfunction "XTAL_P/IO32_8") (pintype "bidirectional"))
    )
    (net (code "76") (name "unconnected-(U2-NC-Pad4)") (class "Default")
      (node (ref "U2") (pin "4") (pinfunction "NC_4") (pintype "no_connect"))
    )
    (net (code "77") (name "unconnected-(U3-R232-Pad15)") (class "Default")
      (node (ref "U3") (pin "15") (pinfunction "R232_15") (pintype "bidirectional"))
    )
    (net (code "78") (name "unconnected-(U3-~{CTS}-Pad9)") (class "Default")
      (node (ref "U3") (pin "9") (pinfunction "~{CTS}_9") (pintype "bidirectional"))
    )
    (net (code "79") (name "unconnected-(U3-~{DCD}-Pad12)") (class "Default")
      (node (ref "U3") (pin "12") (pinfunction "~{DCD}_12") (pintype "bidirectional"))
    )
    (net (code "80") (name "unconnected-(U3-~{DSR}-Pad10)") (class "Default")
      (node (ref "U3") (pin "10") (pinfunction "~{DSR}_10") (pintype "bidirectional"))
    )
    (net (code "81") (name "unconnected-(U3-~{RI}-Pad11)") (class "Default")
      (node (ref "U3") (pin "11") (pinfunction "~{RI}_11") (pintype "bidirectional"))
    )
  )
)
